# prop_breakout.net
KiCad netlist of a schematic drawn in EAGLE
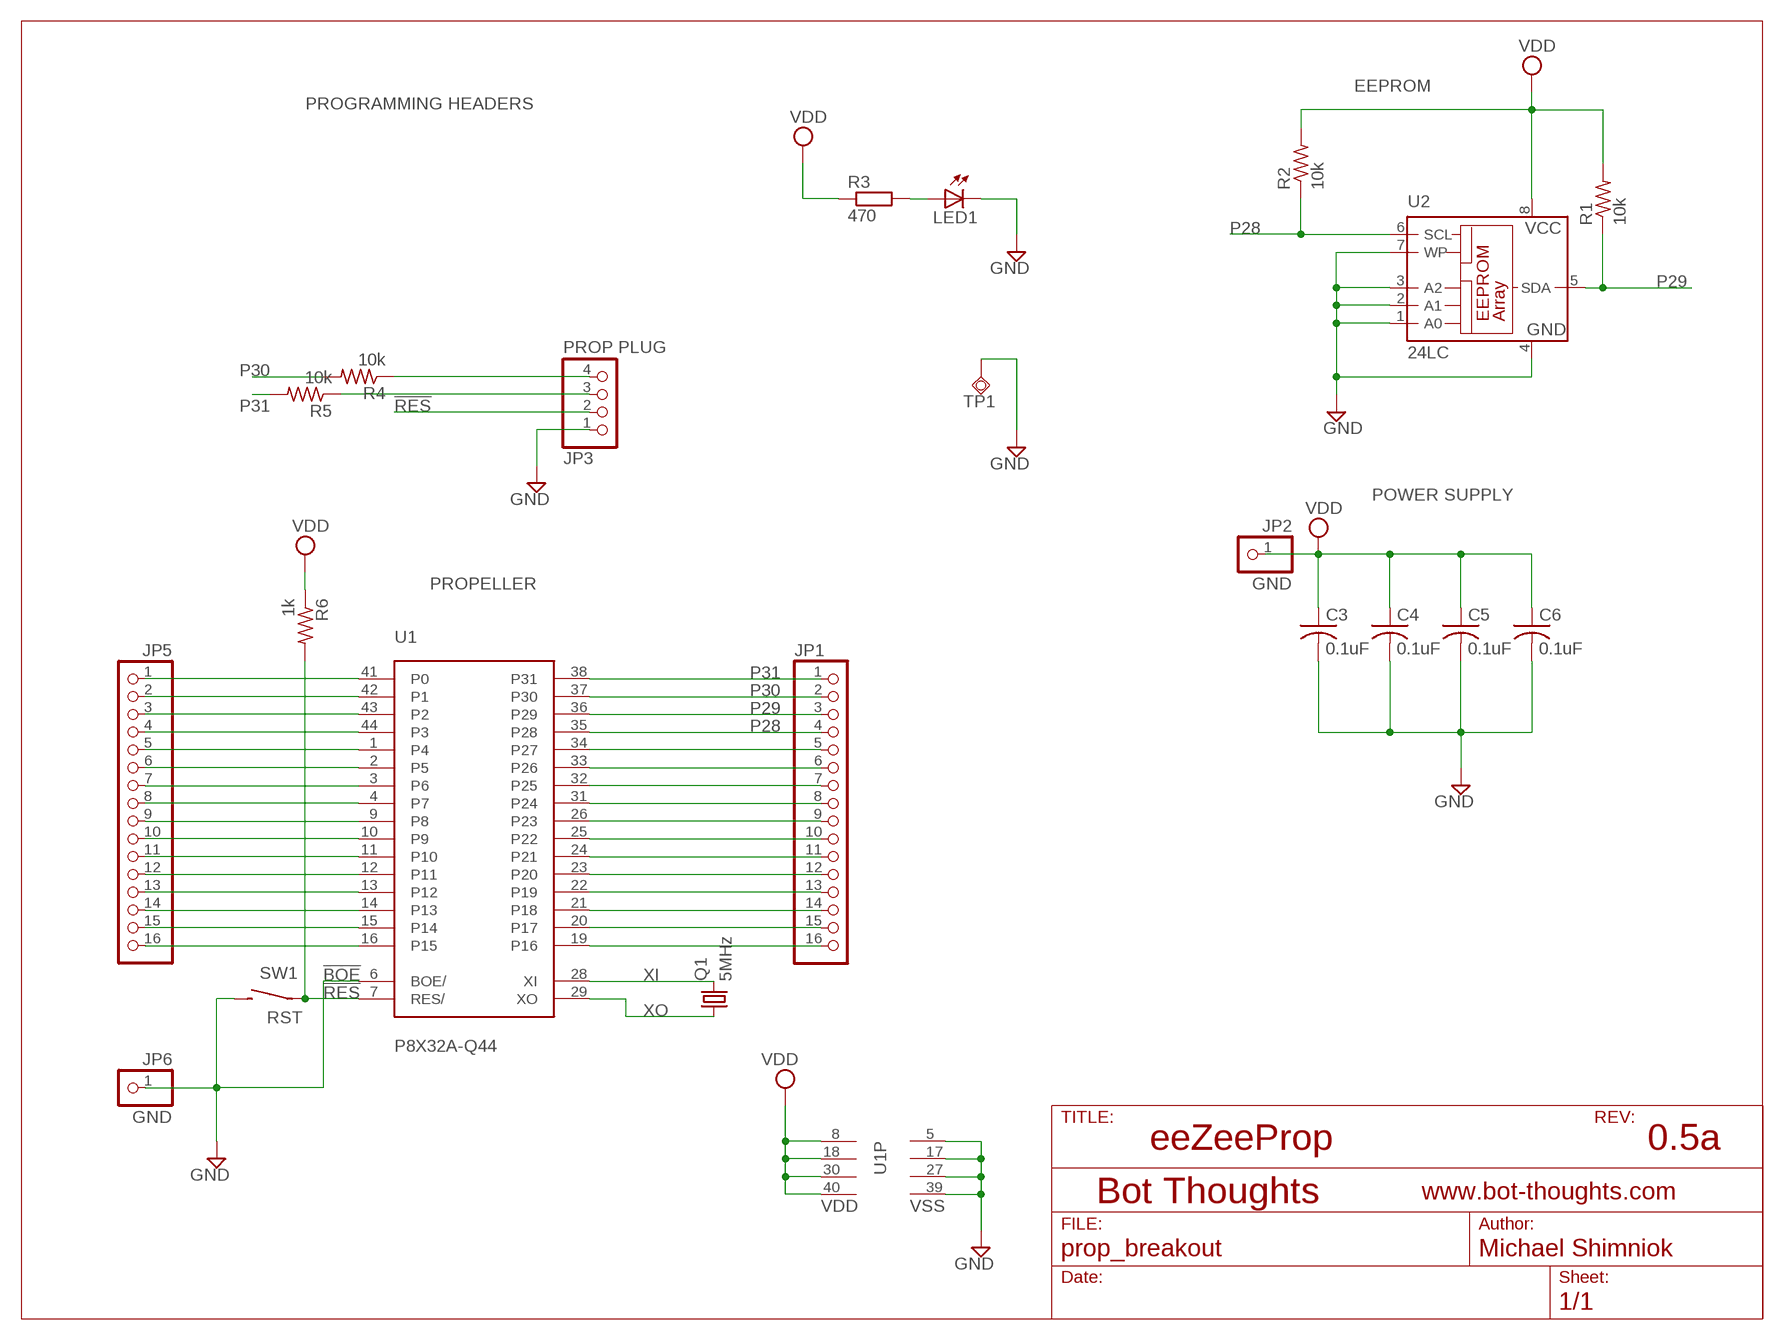
[diagram p0: schematic, sheet 1]

(export (version "E")
  (design (tool "Eeschema 10.0.6"))
  (components
    (comp (ref "C3")
      (value "0.1uF")
      (footprint "eagle-import:C0805")
      (fields (field (name "PARTNO") "0603YC104KAT2A"))
      (libsource (lib "eagle-import") (part "C-USC0805"))
    )
    (comp (ref "C4")
      (value "0.1uF")
      (footprint "eagle-import:C0805")
      (fields (field (name "PARTNO") "0603YC104KAT2A"))
      (libsource (lib "eagle-import") (part "C-USC0805"))
    )
    (comp (ref "C5")
      (value "0.1uF")
      (footprint "eagle-import:C0805")
      (fields (field (name "PARTNO") "0603YC104KAT2A"))
      (libsource (lib "eagle-import") (part "C-USC0805"))
    )
    (comp (ref "C6")
      (value "0.1uF")
      (footprint "eagle-import:C0805")
      (fields (field (name "PARTNO") "0603YC104KAT2A"))
      (libsource (lib "eagle-import") (part "C-USC0805"))
    )
    (comp (ref "JP1")
      (value "PINHD-1X16_2.54-S")
      (footprint "eagle-import:1X16-S")
      (libsource (lib "eagle-import") (part "PINHD-1X16_2.54-S"))
    )
    (comp (ref "JP2")
      (value "GND")
      (footprint "eagle-import:1X01")
      (libsource (lib "eagle-import") (part "PINHD-1X01_2.54"))
    )
    (comp (ref "JP3")
      (value "PROP PLUG")
      (footprint "eagle-import:1X04-S")
      (libsource (lib "eagle-import") (part "PINHD-1X04_2.54-S"))
    )
    (comp (ref "JP5")
      (value "PINHD-1X16_2.54-S")
      (footprint "eagle-import:1X16-S")
      (libsource (lib "eagle-import") (part "PINHD-1X16_2.54-S"))
    )
    (comp (ref "JP6")
      (value "GND")
      (footprint "eagle-import:1X01")
      (libsource (lib "eagle-import") (part "PINHD-1X01_2.54"))
    )
    (comp (ref "LED1")
      (value "0")
      (footprint "eagle-import:CHIPLED_1206")
      (libsource (lib "eagle-import") (part "LEDCHIPLED_1206"))
    )
    (comp (ref "Q1")
      (value "5MHz")
      (footprint "eagle-import:HC49U-V")
      (fields (field (name "OC_FARNELL") "1666969") (field (name "PARTNO") "HC49US-5.000MABJ-UB"))
      (libsource (lib "eagle-import") (part "CRYSTALHC49U-V"))
    )
    (comp (ref "R1")
      (value "10k")
      (footprint "eagle-import:R0805")
      (fields (field (name "PARTNO") "ERJ-3GEYJ103V"))
      (libsource (lib "eagle-import") (part "R-US_R0805"))
    )
    (comp (ref "R2")
      (value "10k")
      (footprint "eagle-import:R0805")
      (fields (field (name "PARTNO") "ERJ-3GEYJ103V"))
      (libsource (lib "eagle-import") (part "R-US_R0805"))
    )
    (comp (ref "R3")
      (value "470")
      (footprint "eagle-import:R0805")
      (libsource (lib "eagle-import") (part "R-EU_R0805"))
    )
    (comp (ref "R4")
      (value "10k")
      (footprint "eagle-import:R0805")
      (fields (field (name "PARTNO") "RC0603JR-071KL"))
      (libsource (lib "eagle-import") (part "R-US_R0805"))
    )
    (comp (ref "R5")
      (value "10k")
      (footprint "eagle-import:R0805")
      (fields (field (name "PARTNO") "RC0603JR-071KL"))
      (libsource (lib "eagle-import") (part "R-US_R0805"))
    )
    (comp (ref "R6")
      (value "1k")
      (footprint "eagle-import:R0805")
      (fields (field (name "PARTNO") "RC0603JR-071KL"))
      (libsource (lib "eagle-import") (part "R-US_R0805"))
    )
    (comp (ref "SW1")
      (value "RST")
      (footprint "eagle-import:6MMTACTILE_RECT")
      (fields (field (name "PARTNO") "MJTP1243"))
      (libsource (lib "eagle-import") (part "SPST_TAC_RECT1"))
    )
    (comp (ref "TP1")
      (value "TPSQTP20R")
      (footprint "eagle-import:TP20R")
      (libsource (lib "eagle-import") (part "TPSQTP20R"))
    )
    (comp (ref "U1")
      (value "P8X32A-Q44")
      (footprint "eagle-import:P8X32A-Q44")
      (fields (field (name "PARTNO") "P8X32A-Q44"))
      (libsource (lib "eagle-import") (part "P8X32A-Q44"))
    )
    (comp (ref "U2")
      (value "24LC")
      (footprint "eagle-import:SO-08")
      (fields
        (field (name "MF") "MICROCHIP")
        (field (name "MPN") "24LC128-I/SNG")
        (field (name "MF_1") "OnSemi")
        (field (name "MPN_1") "CAT24C256WI-GT3")
        (field (name "PARTNO") "CAT24C256WI-GT3")
      )
      (libsource (lib "eagle-import") (part "24SNLC128"))
    )
  )
  (nets
    (net (code "1") (name "/P28") (class "Default")
      (node (ref "JP1") (pin "4") (pinfunction "4_4") (pintype "passive"))
      (node (ref "R2") (pin "1") (pinfunction "1_1") (pintype "passive"))
      (node (ref "U1") (pin "35") (pinfunction "P28_35") (pintype "bidirectional"))
      (node (ref "U2") (pin "6") (pinfunction "SCL_6") (pintype "input"))
    )
    (net (code "2") (name "/P29") (class "Default")
      (node (ref "JP1") (pin "3") (pinfunction "3_3") (pintype "passive"))
      (node (ref "R1") (pin "1") (pinfunction "1_1") (pintype "passive"))
      (node (ref "U1") (pin "36") (pinfunction "P29_36") (pintype "bidirectional"))
      (node (ref "U2") (pin "5") (pinfunction "SDA_5") (pintype "bidirectional"))
    )
    (net (code "3") (name "/P30") (class "Default")
      (node (ref "JP1") (pin "2") (pinfunction "2_2") (pintype "passive"))
      (node (ref "R4") (pin "2") (pinfunction "2_2") (pintype "passive"))
      (node (ref "U1") (pin "37") (pinfunction "P30_37") (pintype "bidirectional"))
    )
    (net (code "4") (name "/P31") (class "Default")
      (node (ref "JP1") (pin "1") (pinfunction "1_1") (pintype "passive"))
      (node (ref "R5") (pin "2") (pinfunction "2_2") (pintype "passive"))
      (node (ref "U1") (pin "38") (pinfunction "P31_38") (pintype "bidirectional"))
    )
    (net (code "5") (name "/XI") (class "Default")
      (node (ref "Q1") (pin "2") (pinfunction "2_2") (pintype "passive"))
      (node (ref "U1") (pin "28") (pinfunction "XI_28") (pintype "input"))
    )
    (net (code "6") (name "/XO") (class "Default")
      (node (ref "Q1") (pin "1") (pinfunction "1_1") (pintype "passive"))
      (node (ref "U1") (pin "29") (pinfunction "XO_29") (pintype "output"))
    )
    (net (code "7") (name "/~{RES}") (class "Default")
      (node (ref "JP3") (pin "2") (pinfunction "2_2") (pintype "passive"))
      (node (ref "R6") (pin "2") (pinfunction "2_2") (pintype "passive"))
      (node (ref "SW1") (pin "P$1") (pinfunction "P_P$1") (pintype "passive"))
      (node (ref "U1") (pin "7") (pinfunction "RES/_7") (pintype "bidirectional"))
    )
    (net (code "8") (name "GND") (class "Default")
      (node (ref "C3") (pin "2") (pinfunction "2_2") (pintype "passive"))
      (node (ref "C4") (pin "2") (pinfunction "2_2") (pintype "passive"))
      (node (ref "C5") (pin "2") (pinfunction "2_2") (pintype "passive"))
      (node (ref "C6") (pin "2") (pinfunction "2_2") (pintype "passive"))
      (node (ref "JP3") (pin "1") (pinfunction "1_1") (pintype "passive"))
      (node (ref "JP6") (pin "1") (pinfunction "1_1") (pintype "passive"))
      (node (ref "LED1") (pin "C") (pinfunction "C_C") (pintype "passive"))
      (node (ref "SW1") (pin "P$2") (pinfunction "S_P$2") (pintype "passive"))
      (node (ref "TP1") (pin "TP") (pinfunction "TP_TP") (pintype "input"))
      (node (ref "U1") (pin "17") (pinfunction "VSS_17") (pintype "power_in"))
      (node (ref "U1") (pin "27") (pinfunction "VSS_27") (pintype "power_in"))
      (node (ref "U1") (pin "39") (pinfunction "VSS_39") (pintype "power_in"))
      (node (ref "U1") (pin "5") (pinfunction "VSS_5") (pintype "power_in"))
      (node (ref "U1") (pin "6") (pinfunction "BOE/_6") (pintype "input"))
      (node (ref "U2") (pin "1") (pinfunction "A0_1") (pintype "input"))
      (node (ref "U2") (pin "2") (pinfunction "A1_2") (pintype "input"))
      (node (ref "U2") (pin "3") (pinfunction "A2_3") (pintype "input"))
      (node (ref "U2") (pin "4") (pinfunction "GND_4") (pintype "power_in"))
      (node (ref "U2") (pin "7") (pinfunction "WP_7") (pintype "input"))
    )
    (net (code "9") (name "Net-(JP3-Pad3)") (class "Default")
      (node (ref "JP3") (pin "3") (pinfunction "3_3") (pintype "passive"))
      (node (ref "R5") (pin "1") (pinfunction "1_1") (pintype "passive"))
    )
    (net (code "10") (name "Net-(JP3-Pad4)") (class "Default")
      (node (ref "JP3") (pin "4") (pinfunction "4_4") (pintype "passive"))
      (node (ref "R4") (pin "1") (pinfunction "1_1") (pintype "passive"))
    )
    (net (code "11") (name "Net-(LED1-PadA)") (class "Default")
      (node (ref "LED1") (pin "A") (pinfunction "A_A") (pintype "passive"))
      (node (ref "R3") (pin "2") (pinfunction "2_2") (pintype "passive"))
    )
    (net (code "12") (name "Net-(U1B-P0)") (class "Default")
      (node (ref "JP5") (pin "1") (pinfunction "1_1") (pintype "passive"))
      (node (ref "U1") (pin "41") (pinfunction "P0_41") (pintype "bidirectional"))
    )
    (net (code "13") (name "Net-(U1B-P1)") (class "Default")
      (node (ref "JP5") (pin "2") (pinfunction "2_2") (pintype "passive"))
      (node (ref "U1") (pin "42") (pinfunction "P1_42") (pintype "bidirectional"))
    )
    (net (code "14") (name "Net-(U1B-P2)") (class "Default")
      (node (ref "JP5") (pin "3") (pinfunction "3_3") (pintype "passive"))
      (node (ref "U1") (pin "43") (pinfunction "P2_43") (pintype "bidirectional"))
    )
    (net (code "15") (name "Net-(U1B-P3)") (class "Default")
      (node (ref "JP5") (pin "4") (pinfunction "4_4") (pintype "passive"))
      (node (ref "U1") (pin "44") (pinfunction "P3_44") (pintype "bidirectional"))
    )
    (net (code "16") (name "Net-(U1B-P4)") (class "Default")
      (node (ref "JP5") (pin "5") (pinfunction "5_5") (pintype "passive"))
      (node (ref "U1") (pin "1") (pinfunction "P4_1") (pintype "bidirectional"))
    )
    (net (code "17") (name "Net-(U1B-P5)") (class "Default")
      (node (ref "JP5") (pin "6") (pinfunction "6_6") (pintype "passive"))
      (node (ref "U1") (pin "2") (pinfunction "P5_2") (pintype "bidirectional"))
    )
    (net (code "18") (name "Net-(U1B-P6)") (class "Default")
      (node (ref "JP5") (pin "7") (pinfunction "7_7") (pintype "passive"))
      (node (ref "U1") (pin "3") (pinfunction "P6_3") (pintype "bidirectional"))
    )
    (net (code "19") (name "Net-(U1B-P7)") (class "Default")
      (node (ref "JP5") (pin "8") (pinfunction "8_8") (pintype "passive"))
      (node (ref "U1") (pin "4") (pinfunction "P7_4") (pintype "bidirectional"))
    )
    (net (code "20") (name "Net-(U1B-P8)") (class "Default")
      (node (ref "JP5") (pin "9") (pinfunction "9_9") (pintype "passive"))
      (node (ref "U1") (pin "9") (pinfunction "P8_9") (pintype "bidirectional"))
    )
    (net (code "21") (name "Net-(U1B-P9)") (class "Default")
      (node (ref "JP5") (pin "10") (pinfunction "10_10") (pintype "passive"))
      (node (ref "U1") (pin "10") (pinfunction "P9_10") (pintype "bidirectional"))
    )
    (net (code "22") (name "Net-(U1B-P10)") (class "Default")
      (node (ref "JP5") (pin "11") (pinfunction "11_11") (pintype "passive"))
      (node (ref "U1") (pin "11") (pinfunction "P10_11") (pintype "bidirectional"))
    )
    (net (code "23") (name "Net-(U1B-P11)") (class "Default")
      (node (ref "JP5") (pin "12") (pinfunction "12_12") (pintype "passive"))
      (node (ref "U1") (pin "12") (pinfunction "P11_12") (pintype "bidirectional"))
    )
    (net (code "24") (name "Net-(U1B-P12)") (class "Default")
      (node (ref "JP5") (pin "13") (pinfunction "13_13") (pintype "passive"))
      (node (ref "U1") (pin "13") (pinfunction "P12_13") (pintype "bidirectional"))
    )
    (net (code "25") (name "Net-(U1B-P13)") (class "Default")
      (node (ref "JP5") (pin "14") (pinfunction "14_14") (pintype "passive"))
      (node (ref "U1") (pin "14") (pinfunction "P13_14") (pintype "bidirectional"))
    )
    (net (code "26") (name "Net-(U1B-P14)") (class "Default")
      (node (ref "JP5") (pin "15") (pinfunction "15_15") (pintype "passive"))
      (node (ref "U1") (pin "15") (pinfunction "P14_15") (pintype "bidirectional"))
    )
    (net (code "27") (name "Net-(U1B-P15)") (class "Default")
      (node (ref "JP5") (pin "16") (pinfunction "16_16") (pintype "passive"))
      (node (ref "U1") (pin "16") (pinfunction "P15_16") (pintype "bidirectional"))
    )
    (net (code "28") (name "Net-(U1B-P16)") (class "Default")
      (node (ref "JP1") (pin "16") (pinfunction "16_16") (pintype "passive"))
      (node (ref "U1") (pin "19") (pinfunction "P16_19") (pintype "bidirectional"))
    )
    (net (code "29") (name "Net-(U1B-P17)") (class "Default")
      (node (ref "JP1") (pin "15") (pinfunction "15_15") (pintype "passive"))
      (node (ref "U1") (pin "20") (pinfunction "P17_20") (pintype "bidirectional"))
    )
    (net (code "30") (name "Net-(U1B-P18)") (class "Default")
      (node (ref "JP1") (pin "14") (pinfunction "14_14") (pintype "passive"))
      (node (ref "U1") (pin "21") (pinfunction "P18_21") (pintype "bidirectional"))
    )
    (net (code "31") (name "Net-(U1B-P19)") (class "Default")
      (node (ref "JP1") (pin "13") (pinfunction "13_13") (pintype "passive"))
      (node (ref "U1") (pin "22") (pinfunction "P19_22") (pintype "bidirectional"))
    )
    (net (code "32") (name "Net-(U1B-P20)") (class "Default")
      (node (ref "JP1") (pin "12") (pinfunction "12_12") (pintype "passive"))
      (node (ref "U1") (pin "23") (pinfunction "P20_23") (pintype "bidirectional"))
    )
    (net (code "33") (name "Net-(U1B-P21)") (class "Default")
      (node (ref "JP1") (pin "11") (pinfunction "11_11") (pintype "passive"))
      (node (ref "U1") (pin "24") (pinfunction "P21_24") (pintype "bidirectional"))
    )
    (net (code "34") (name "Net-(U1B-P22)") (class "Default")
      (node (ref "JP1") (pin "10") (pinfunction "10_10") (pintype "passive"))
      (node (ref "U1") (pin "25") (pinfunction "P22_25") (pintype "bidirectional"))
    )
    (net (code "35") (name "Net-(U1B-P23)") (class "Default")
      (node (ref "JP1") (pin "9") (pinfunction "9_9") (pintype "passive"))
      (node (ref "U1") (pin "26") (pinfunction "P23_26") (pintype "bidirectional"))
    )
    (net (code "36") (name "Net-(U1B-P24)") (class "Default")
      (node (ref "JP1") (pin "8") (pinfunction "8_8") (pintype "passive"))
      (node (ref "U1") (pin "31") (pinfunction "P24_31") (pintype "bidirectional"))
    )
    (net (code "37") (name "Net-(U1B-P25)") (class "Default")
      (node (ref "JP1") (pin "7") (pinfunction "7_7") (pintype "passive"))
      (node (ref "U1") (pin "32") (pinfunction "P25_32") (pintype "bidirectional"))
    )
    (net (code "38") (name "Net-(U1B-P26)") (class "Default")
      (node (ref "JP1") (pin "6") (pinfunction "6_6") (pintype "passive"))
      (node (ref "U1") (pin "33") (pinfunction "P26_33") (pintype "bidirectional"))
    )
    (net (code "39") (name "Net-(U1B-P27)") (class "Default")
      (node (ref "JP1") (pin "5") (pinfunction "5_5") (pintype "passive"))
      (node (ref "U1") (pin "34") (pinfunction "P27_34") (pintype "bidirectional"))
    )
    (net (code "40") (name "VDD") (class "Default")
      (node (ref "C3") (pin "1") (pinfunction "1_1") (pintype "passive"))
      (node (ref "C4") (pin "1") (pinfunction "1_1") (pintype "passive"))
      (node (ref "C5") (pin "1") (pinfunction "1_1") (pintype "passive"))
      (node (ref "C6") (pin "1") (pinfunction "1_1") (pintype "passive"))
      (node (ref "JP2") (pin "1") (pinfunction "1_1") (pintype "passive"))
      (node (ref "R1") (pin "2") (pinfunction "2_2") (pintype "passive"))
      (node (ref "R2") (pin "2") (pinfunction "2_2") (pintype "passive"))
      (node (ref "R3") (pin "1") (pinfunction "1_1") (pintype "passive"))
      (node (ref "R6") (pin "1") (pinfunction "1_1") (pintype "passive"))
      (node (ref "U1") (pin "18") (pinfunction "VDD_18") (pintype "power_in"))
      (node (ref "U1") (pin "30") (pinfunction "VDD_30") (pintype "power_in"))
      (node (ref "U1") (pin "40") (pinfunction "VDD_40") (pintype "power_in"))
      (node (ref "U1") (pin "8") (pinfunction "VDD_8") (pintype "power_in"))
      (node (ref "U2") (pin "8") (pinfunction "VCC_8") (pintype "power_in"))
    )
  )
)
